# Proximity_Sensors.net
KiCad netlist of a schematic drawn in Altium Designer
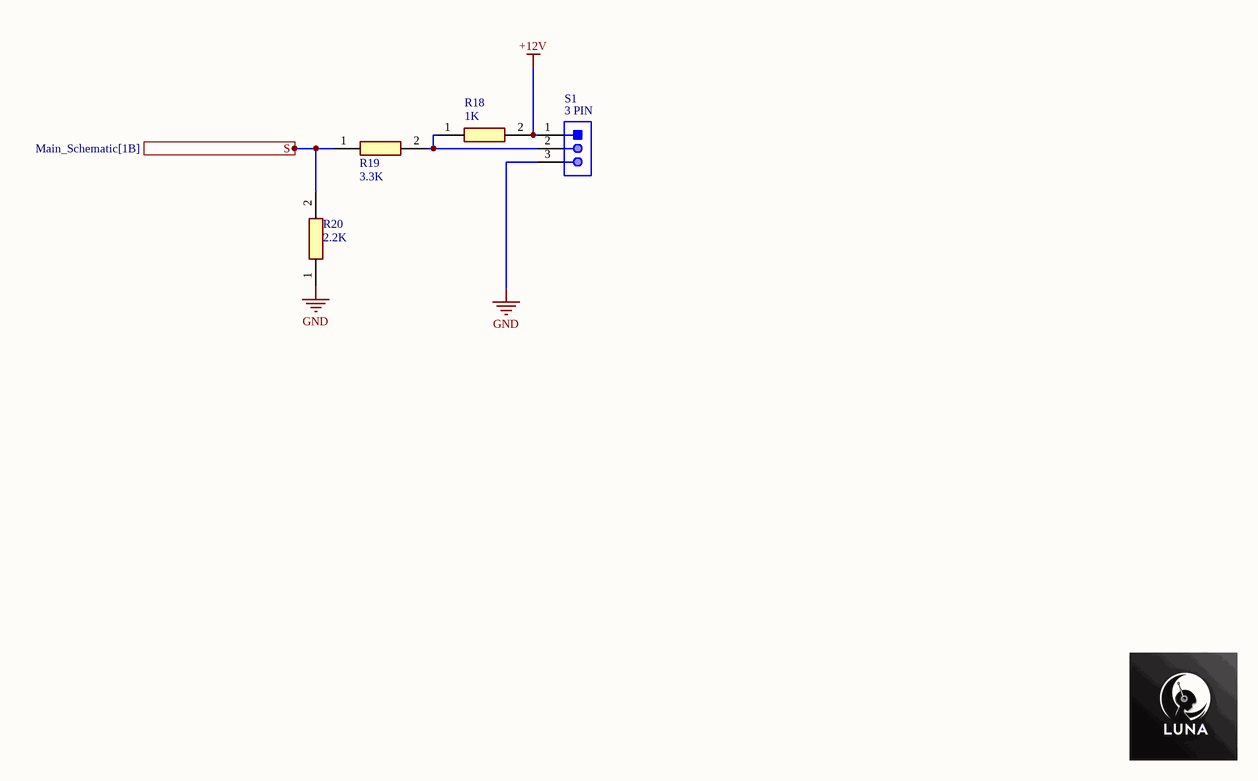
[diagram p0: Proximity Sensors.SchDoc]

(export (version "E")
  (design (tool "Eeschema 10.0.6"))
  (components
    (comp (ref "R18")
      (value "1K")
      (footprint "SamacSys:RESC1608X55N")
      (description "Resistor")
      (fields
        (field (name "MANUFACTURER_PART_NUMBER") "RC0603FR-071KL")
        (field (name "MOUSER PART NUMBER") "603-RC0603FR-071KL")
      )
      (libsource (lib "SamacSys") (part "RC0603FR-071KL"))
    )
    (comp (ref "R19")
      (value "3.3K")
      (footprint "SamacSys:RESC1608X55N")
      (description "Resistor RMCF0603JT3K30")
      (fields (field (name "MANUFACTURER_PART_NUMBER") "RMCF0603JT3K30"))
      (libsource (lib "*") (part "RMCF0603JT3K30"))
    )
    (comp (ref "R20")
      (value "2.2K")
      (footprint "SamacSys:ERJ3EKF1000V")
      (description "Resistor")
      (fields (field (name "MANUFACTURER_PART_NUMBER") "ERJ3GEYJ222V"))
      (libsource (lib "*") (part "ERJ3GEYJ222V"))
    )
    (comp (ref "S1")
      (value "3 PIN")
      (footprint "TECO-171825-3_V")
      (fields (field (name "MANUFACTURER") "TE Connectivity"))
      (libsource (lib "Altium Content Vault") (part "CN-1P-M-R3"))
    )
  )
  (nets
    (net (code "1") (name "+12V") (class "Default")
      (node (ref "R18") (pin "2") (pinfunction "2_2") (pintype "passive"))
      (node (ref "S1") (pin "1") (pinfunction "1_1") (pintype "passive"))
    )
    (net (code "2") (name "/S") (class "Default")
      (node (ref "R19") (pin "1") (pinfunction "1_1") (pintype "passive"))
      (node (ref "R20") (pin "2") (pinfunction "2_2") (pintype "passive"))
    )
    (net (code "3") (name "GND") (class "Default")
      (node (ref "R20") (pin "1") (pinfunction "1_1") (pintype "passive"))
      (node (ref "S1") (pin "3") (pinfunction "3_3") (pintype "passive"))
    )
    (net (code "4") (name "Net-(R18-Pad1)") (class "Default")
      (node (ref "R18") (pin "1") (pinfunction "1_1") (pintype "passive"))
      (node (ref "R19") (pin "2") (pinfunction "2_2") (pintype "passive"))
      (node (ref "S1") (pin "2") (pinfunction "2_2") (pintype "passive"))
    )
  )
)
